# shared_pcb.net
KiCad netlist of a schematic drawn in EAGLE
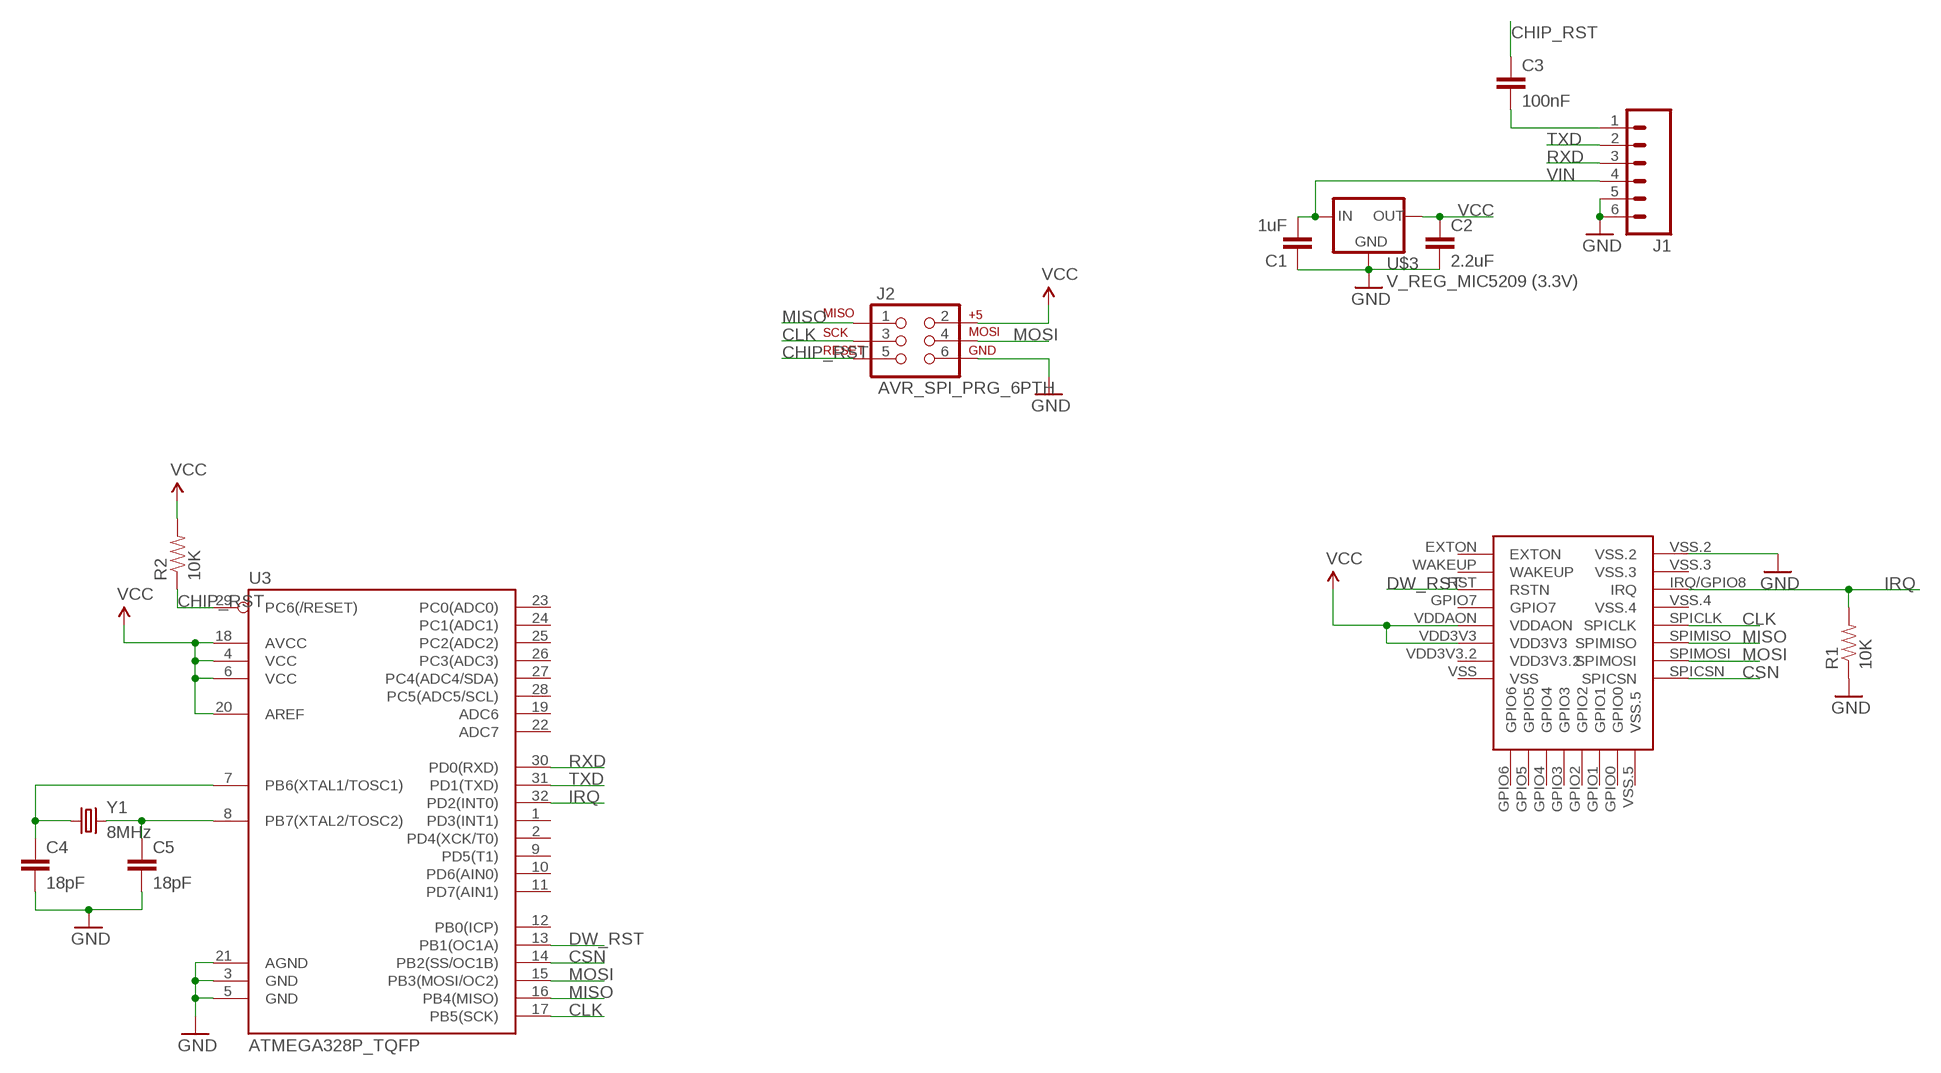
[diagram p0: schematic, sheet 1]

(export (version "E")
  (design (tool "Eeschema 10.0.6"))
  (components
    (comp (ref "C1")
      (value "1uF")
      (footprint "eagle-import:1206")
      (libsource (lib "eagle-import") (part "CAP1206"))
    )
    (comp (ref "C2")
      (value "2.2uF")
      (footprint "eagle-import:1206")
      (libsource (lib "eagle-import") (part "CAP1206"))
    )
    (comp (ref "C3")
      (value "100nF")
      (footprint "eagle-import:1206")
      (libsource (lib "eagle-import") (part "CAP1206"))
    )
    (comp (ref "C4")
      (value "18pF")
      (footprint "eagle-import:1206")
      (libsource (lib "eagle-import") (part "CAP1206"))
    )
    (comp (ref "C5")
      (value "18pF")
      (footprint "eagle-import:1206")
      (libsource (lib "eagle-import") (part "CAP1206"))
    )
    (comp (ref "J1")
      (value "M06LOCK")
      (footprint "eagle-import:1X06_LOCK")
      (libsource (lib "eagle-import") (part "M06LOCK"))
    )
    (comp (ref "J2")
      (value "AVR_SPI_PRG_6PTH")
      (footprint "eagle-import:2X3")
      (libsource (lib "eagle-import") (part "AVR_SPI_PRG_6PTH"))
    )
    (comp (ref "R1")
      (value "10K")
      (footprint "eagle-import:1206")
      (libsource (lib "eagle-import") (part "RESISTOR1206"))
    )
    (comp (ref "R2")
      (value "10K")
      (footprint "eagle-import:1206")
      (libsource (lib "eagle-import") (part "RESISTOR1206"))
    )
    (comp (ref "U$1")
      (value "DWM1000")
      (footprint "eagle-import:DWM1000")
      (libsource (lib "eagle-import") (part "DWM1000"))
    )
    (comp (ref "U$3")
      (value "V_REG_MIC5209 (3.3V)")
      (footprint "eagle-import:SOT223")
      (libsource (lib "eagle-import") (part "V_REG_MIC2920"))
    )
    (comp (ref "U3")
      (value "ATMEGA328P_TQFP")
      (footprint "eagle-import:TQFP32-08")
      (libsource (lib "eagle-import") (part "ATMEGA328P_TQFP"))
    )
    (comp (ref "Y1")
      (value "8MHz")
      (footprint "eagle-import:CRYSTAL-TXC-7A")
      (libsource (lib "eagle-import") (part "CRYSTALTXC-7A"))
    )
  )
  (nets
    (net (code "1") (name "/CHIP_RST") (class "Default")
      (node (ref "C3") (pin "1") (pinfunction "1_1") (pintype "passive"))
      (node (ref "J2") (pin "5") (pinfunction "5_5") (pintype "passive"))
      (node (ref "R2") (pin "1") (pinfunction "1_1") (pintype "passive"))
      (node (ref "U3") (pin "29") (pinfunction "PC6(/RESET)_29") (pintype "bidirectional"))
    )
    (net (code "2") (name "/CLK") (class "Default")
      (node (ref "J2") (pin "3") (pinfunction "3_3") (pintype "passive"))
      (node (ref "U$1") (pin "SPICLK") (pinfunction "SPICLK_SPICLK") (pintype "bidirectional"))
      (node (ref "U3") (pin "17") (pinfunction "PB5(SCK)_17") (pintype "bidirectional"))
    )
    (net (code "3") (name "/CSN") (class "Default")
      (node (ref "U$1") (pin "SPICSN") (pinfunction "SPICSN_SPICSN") (pintype "bidirectional"))
      (node (ref "U3") (pin "14") (pinfunction "PB2(SS/OC1B)_14") (pintype "bidirectional"))
    )
    (net (code "4") (name "/DW_RST") (class "Default")
      (node (ref "U$1") (pin "RST") (pinfunction "RSTN_RST") (pintype "bidirectional"))
      (node (ref "U3") (pin "13") (pinfunction "PB1(OC1A)_13") (pintype "bidirectional"))
    )
    (net (code "5") (name "/IRQ") (class "Default")
      (node (ref "R1") (pin "2") (pinfunction "2_2") (pintype "passive"))
      (node (ref "U$1") (pin "IRQ/GPIO8") (pinfunction "IRQ_IRQ/GPIO8") (pintype "bidirectional"))
      (node (ref "U3") (pin "32") (pinfunction "PD2(INT0)_32") (pintype "bidirectional"))
    )
    (net (code "6") (name "/MISO") (class "Default")
      (node (ref "J2") (pin "1") (pinfunction "1_1") (pintype "passive"))
      (node (ref "U$1") (pin "SPIMISO") (pinfunction "SPIMISO_SPIMISO") (pintype "bidirectional"))
      (node (ref "U3") (pin "16") (pinfunction "PB4(MISO)_16") (pintype "bidirectional"))
    )
    (net (code "7") (name "/MOSI") (class "Default")
      (node (ref "J2") (pin "4") (pinfunction "4_4") (pintype "passive"))
      (node (ref "U$1") (pin "SPIMOSI") (pinfunction "SPIMOSI_SPIMOSI") (pintype "bidirectional"))
      (node (ref "U3") (pin "15") (pinfunction "PB3(MOSI/OC2)_15") (pintype "bidirectional"))
    )
    (net (code "8") (name "/RXD") (class "Default")
      (node (ref "J1") (pin "3") (pinfunction "3_3") (pintype "passive"))
      (node (ref "U3") (pin "30") (pinfunction "PD0(RXD)_30") (pintype "bidirectional"))
    )
    (net (code "9") (name "/TXD") (class "Default")
      (node (ref "J1") (pin "2") (pinfunction "2_2") (pintype "passive"))
      (node (ref "U3") (pin "31") (pinfunction "PD1(TXD)_31") (pintype "bidirectional"))
    )
    (net (code "10") (name "/VIN") (class "Default")
      (node (ref "C1") (pin "2") (pinfunction "2_2") (pintype "passive"))
      (node (ref "J1") (pin "4") (pinfunction "4_4") (pintype "passive"))
      (node (ref "U$3") (pin "1") (pinfunction "IN_1") (pintype "input"))
    )
    (net (code "11") (name "GND") (class "Default")
      (node (ref "C1") (pin "1") (pinfunction "1_1") (pintype "passive"))
      (node (ref "C2") (pin "2") (pinfunction "2_2") (pintype "passive"))
      (node (ref "C4") (pin "2") (pinfunction "2_2") (pintype "passive"))
      (node (ref "C5") (pin "2") (pinfunction "2_2") (pintype "passive"))
      (node (ref "J1") (pin "5") (pinfunction "5_5") (pintype "passive"))
      (node (ref "J1") (pin "6") (pinfunction "6_6") (pintype "passive"))
      (node (ref "J2") (pin "6") (pinfunction "6_6") (pintype "passive"))
      (node (ref "R1") (pin "1") (pinfunction "1_1") (pintype "passive"))
      (node (ref "U$1") (pin "VSS.2") (pinfunction "VSS.2_VSS.2") (pintype "bidirectional"))
      (node (ref "U$3") (pin "2") (pinfunction "GND_2") (pintype "input"))
      (node (ref "U3") (pin "21") (pinfunction "AGND_21") (pintype "bidirectional"))
      (node (ref "U3") (pin "3") (pinfunction "GND_3") (pintype "bidirectional"))
      (node (ref "U3") (pin "5") (pinfunction "GND_5") (pintype "bidirectional"))
    )
    (net (code "12") (name "Net-(C3-Pad2)") (class "Default")
      (node (ref "C3") (pin "2") (pinfunction "2_2") (pintype "passive"))
      (node (ref "J1") (pin "1") (pinfunction "1_1") (pintype "passive"))
    )
    (net (code "13") (name "Net-(U3-PB6(XTAL1{slash}TOSC1))") (class "Default")
      (node (ref "C4") (pin "1") (pinfunction "1_1") (pintype "passive"))
      (node (ref "U3") (pin "7") (pinfunction "PB6(XTAL1/TOSC1)_7") (pintype "bidirectional"))
      (node (ref "Y1") (pin "P$1") (pinfunction "1_P$1") (pintype "passive"))
    )
    (net (code "14") (name "Net-(U3-PB7(XTAL2{slash}TOSC2))") (class "Default")
      (node (ref "C5") (pin "1") (pinfunction "1_1") (pintype "passive"))
      (node (ref "U3") (pin "8") (pinfunction "PB7(XTAL2/TOSC2)_8") (pintype "bidirectional"))
      (node (ref "Y1") (pin "P$2") (pinfunction "2_P$2") (pintype "passive"))
    )
    (net (code "15") (name "VCC") (class "Default")
      (node (ref "C2") (pin "1") (pinfunction "1_1") (pintype "passive"))
      (node (ref "J2") (pin "2") (pinfunction "2_2") (pintype "passive"))
      (node (ref "R2") (pin "2") (pinfunction "2_2") (pintype "passive"))
      (node (ref "U$1") (pin "VDD3V3") (pinfunction "VDD3V3_VDD3V3") (pintype "bidirectional"))
      (node (ref "U$1") (pin "VDDAON") (pinfunction "VDDAON_VDDAON") (pintype "bidirectional"))
      (node (ref "U$3") (pin "3") (pinfunction "OUT_3") (pintype "passive"))
      (node (ref "U3") (pin "18") (pinfunction "AVCC_18") (pintype "bidirectional"))
      (node (ref "U3") (pin "20") (pinfunction "AREF_20") (pintype "bidirectional"))
      (node (ref "U3") (pin "4") (pinfunction "VCC_4") (pintype "bidirectional"))
      (node (ref "U3") (pin "6") (pinfunction "VCC_6") (pintype "bidirectional"))
    )
    (net (code "16") (name "unconnected-(U$1-PadEXTON)") (class "Default")
      (node (ref "U$1") (pin "EXTON") (pinfunction "EXTON_EXTON") (pintype "bidirectional"))
    )
    (net (code "17") (name "unconnected-(U$1-PadGPIO0)") (class "Default")
      (node (ref "U$1") (pin "GPIO0") (pinfunction "GPIO0_GPIO0") (pintype "bidirectional"))
    )
    (net (code "18") (name "unconnected-(U$1-PadGPIO1)") (class "Default")
      (node (ref "U$1") (pin "GPIO1") (pinfunction "GPIO1_GPIO1") (pintype "bidirectional"))
    )
    (net (code "19") (name "unconnected-(U$1-PadGPIO2)") (class "Default")
      (node (ref "U$1") (pin "GPIO2") (pinfunction "GPIO2_GPIO2") (pintype "bidirectional"))
    )
    (net (code "20") (name "unconnected-(U$1-PadGPIO3)") (class "Default")
      (node (ref "U$1") (pin "GPIO3") (pinfunction "GPIO3_GPIO3") (pintype "bidirectional"))
    )
    (net (code "21") (name "unconnected-(U$1-PadGPIO4)") (class "Default")
      (node (ref "U$1") (pin "GPIO4") (pinfunction "GPIO4_GPIO4") (pintype "bidirectional"))
    )
    (net (code "22") (name "unconnected-(U$1-PadGPIO5)") (class "Default")
      (node (ref "U$1") (pin "GPIO5") (pinfunction "GPIO5_GPIO5") (pintype "bidirectional"))
    )
    (net (code "23") (name "unconnected-(U$1-PadGPIO6)") (class "Default")
      (node (ref "U$1") (pin "GPIO6") (pinfunction "GPIO6_GPIO6") (pintype "bidirectional"))
    )
    (net (code "24") (name "unconnected-(U$1-PadGPIO7)") (class "Default")
      (node (ref "U$1") (pin "GPIO7") (pinfunction "GPIO7_GPIO7") (pintype "bidirectional"))
    )
    (net (code "25") (name "unconnected-(U$1-PadVDD3V3.2)") (class "Default")
      (node (ref "U$1") (pin "VDD3V3.2") (pinfunction "VDD3V3.2_VDD3V3.2") (pintype "bidirectional"))
    )
    (net (code "26") (name "unconnected-(U$1-PadVSS)") (class "Default")
      (node (ref "U$1") (pin "VSS") (pinfunction "VSS_VSS") (pintype "bidirectional"))
    )
    (net (code "27") (name "unconnected-(U$1-PadVSS.3)") (class "Default")
      (node (ref "U$1") (pin "VSS.3") (pinfunction "VSS.3_VSS.3") (pintype "bidirectional"))
    )
    (net (code "28") (name "unconnected-(U$1-PadVSS.4)") (class "Default")
      (node (ref "U$1") (pin "VSS.4") (pinfunction "VSS.4_VSS.4") (pintype "bidirectional"))
    )
    (net (code "29") (name "unconnected-(U$1-PadVSS.5)") (class "Default")
      (node (ref "U$1") (pin "VSS.5") (pinfunction "VSS.5_VSS.5") (pintype "bidirectional"))
    )
    (net (code "30") (name "unconnected-(U$1-PadWAKEUP)") (class "Default")
      (node (ref "U$1") (pin "WAKEUP") (pinfunction "WAKEUP_WAKEUP") (pintype "bidirectional"))
    )
    (net (code "31") (name "unconnected-(U3-ADC6-Pad19)") (class "Default")
      (node (ref "U3") (pin "19") (pinfunction "ADC6_19") (pintype "bidirectional"))
    )
    (net (code "32") (name "unconnected-(U3-ADC7-Pad22)") (class "Default")
      (node (ref "U3") (pin "22") (pinfunction "ADC7_22") (pintype "bidirectional"))
    )
    (net (code "33") (name "unconnected-(U3-PB0(ICP)-Pad12)") (class "Default")
      (node (ref "U3") (pin "12") (pinfunction "PB0(ICP)_12") (pintype "bidirectional"))
    )
    (net (code "34") (name "unconnected-(U3-PC0(ADC0)-Pad23)") (class "Default")
      (node (ref "U3") (pin "23") (pinfunction "PC0(ADC0)_23") (pintype "bidirectional"))
    )
    (net (code "35") (name "unconnected-(U3-PC1(ADC1)-Pad24)") (class "Default")
      (node (ref "U3") (pin "24") (pinfunction "PC1(ADC1)_24") (pintype "bidirectional"))
    )
    (net (code "36") (name "unconnected-(U3-PC2(ADC2)-Pad25)") (class "Default")
      (node (ref "U3") (pin "25") (pinfunction "PC2(ADC2)_25") (pintype "bidirectional"))
    )
    (net (code "37") (name "unconnected-(U3-PC3(ADC3)-Pad26)") (class "Default")
      (node (ref "U3") (pin "26") (pinfunction "PC3(ADC3)_26") (pintype "bidirectional"))
    )
    (net (code "38") (name "unconnected-(U3-PC4(ADC4{slash}SDA)-Pad27)") (class "Default")
      (node (ref "U3") (pin "27") (pinfunction "PC4(ADC4/SDA)_27") (pintype "bidirectional"))
    )
    (net (code "39") (name "unconnected-(U3-PC5(ADC5{slash}SCL)-Pad28)") (class "Default")
      (node (ref "U3") (pin "28") (pinfunction "PC5(ADC5/SCL)_28") (pintype "bidirectional"))
    )
    (net (code "40") (name "unconnected-(U3-PD3(INT1)-Pad1)") (class "Default")
      (node (ref "U3") (pin "1") (pinfunction "PD3(INT1)_1") (pintype "bidirectional"))
    )
    (net (code "41") (name "unconnected-(U3-PD4(XCK{slash}T0)-Pad2)") (class "Default")
      (node (ref "U3") (pin "2") (pinfunction "PD4(XCK/T0)_2") (pintype "bidirectional"))
    )
    (net (code "42") (name "unconnected-(U3-PD5(T1)-Pad9)") (class "Default")
      (node (ref "U3") (pin "9") (pinfunction "PD5(T1)_9") (pintype "bidirectional"))
    )
    (net (code "43") (name "unconnected-(U3-PD6(AIN0)-Pad10)") (class "Default")
      (node (ref "U3") (pin "10") (pinfunction "PD6(AIN0)_10") (pintype "bidirectional"))
    )
    (net (code "44") (name "unconnected-(U3-PD7(AIN1)-Pad11)") (class "Default")
      (node (ref "U3") (pin "11") (pinfunction "PD7(AIN1)_11") (pintype "bidirectional"))
    )
  )
)
